# WasteInfoBoard_V_1_2.net
KiCad netlist of a schematic drawn in EAGLE
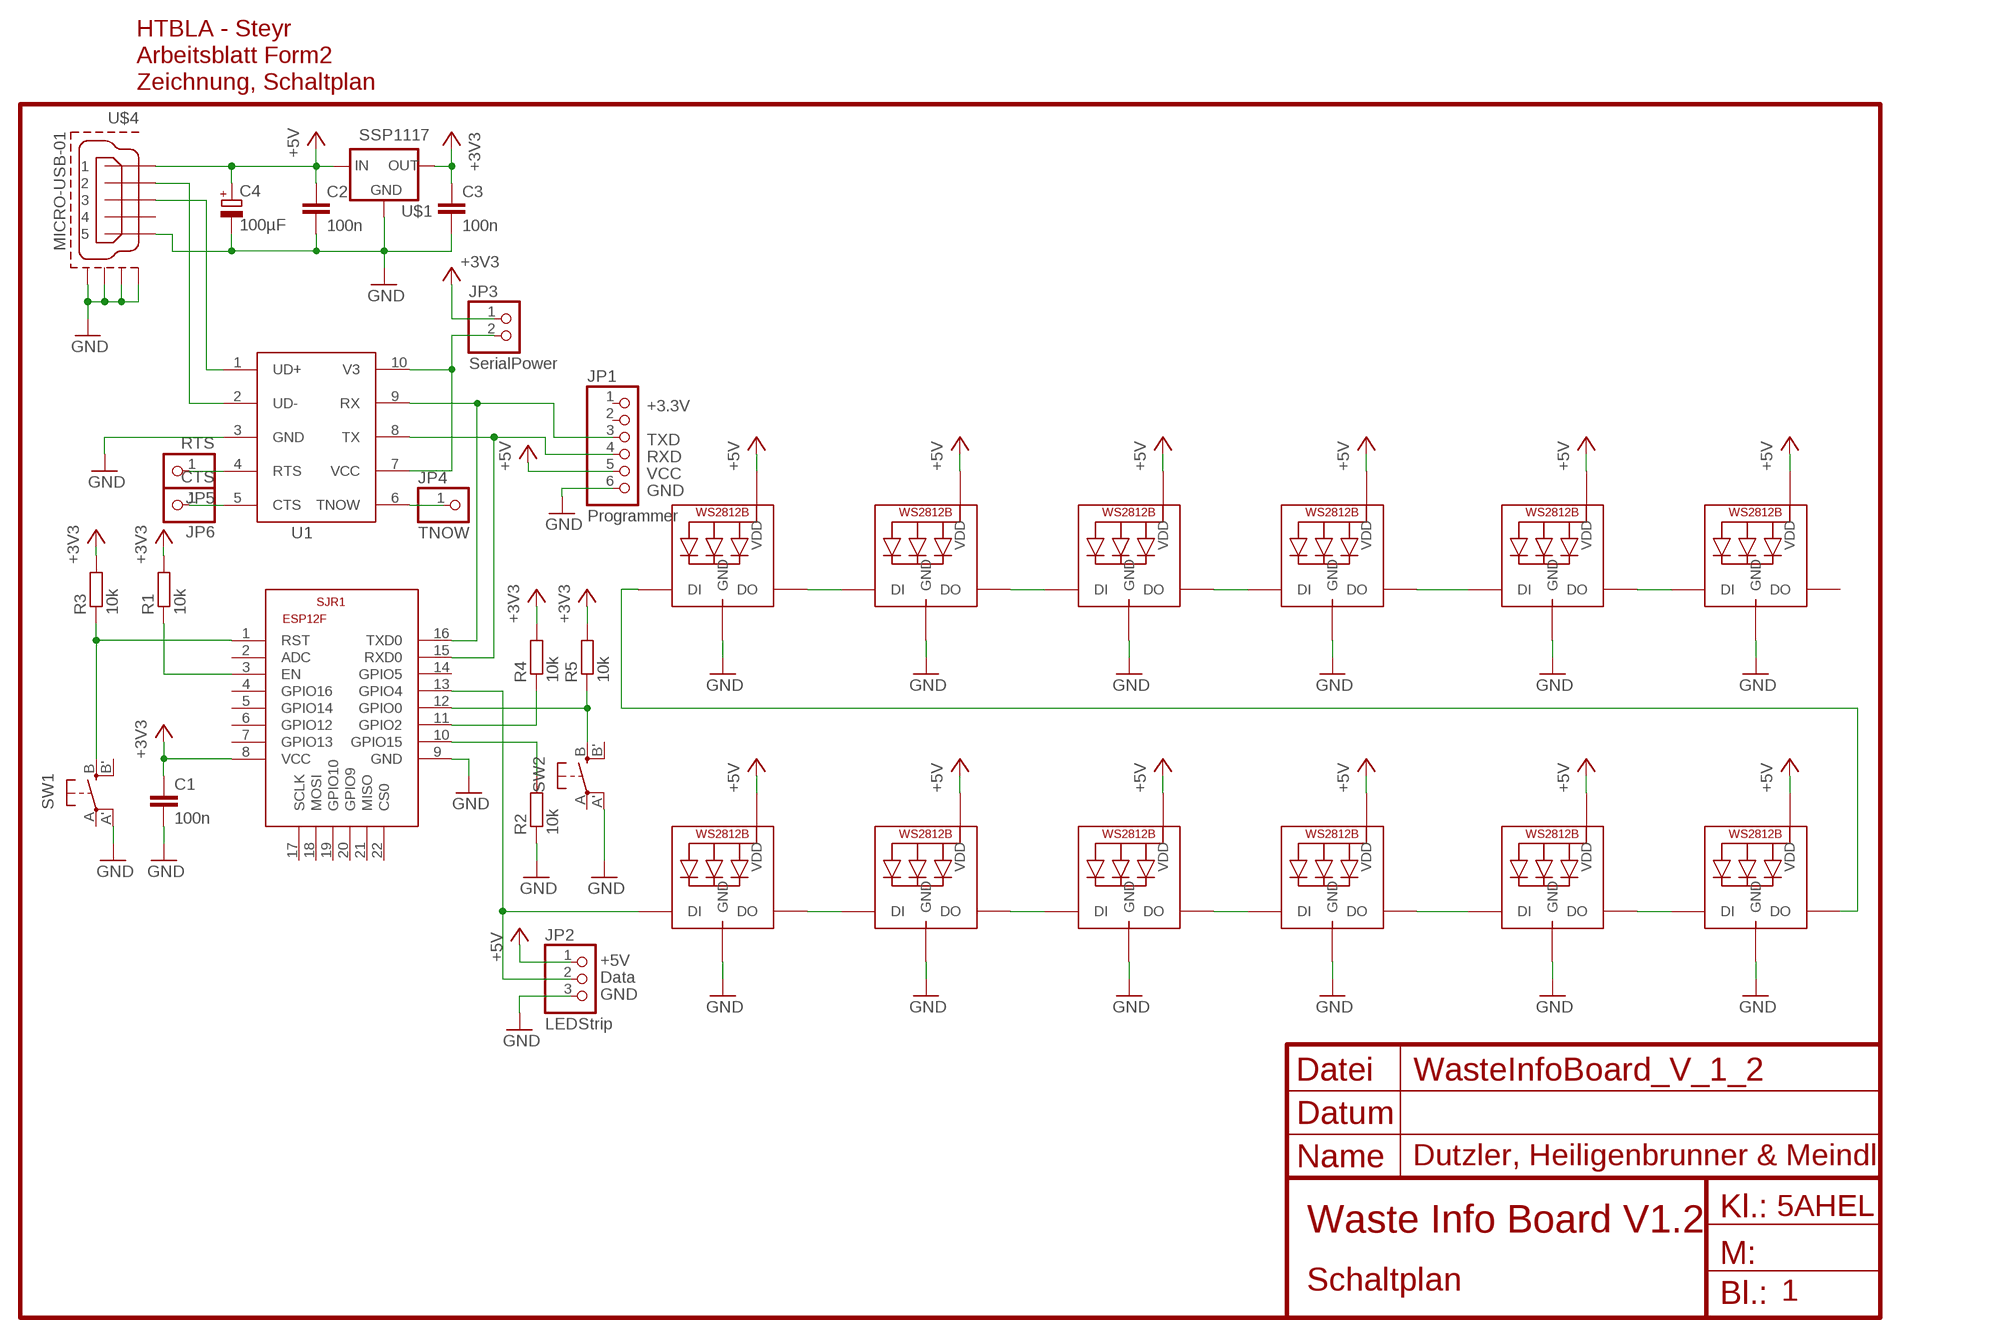
[diagram p0: schematic, sheet 1]

(export (version "E")
  (design (tool "Eeschema 10.0.6"))
  (components
    (comp (ref "C1")
      (value "100n")
      (footprint "eagle-import:C0805")
      (libsource (lib "eagle-import") (part "C-EUC0805"))
    )
    (comp (ref "C2")
      (value "100n")
      (footprint "eagle-import:C0805")
      (libsource (lib "eagle-import") (part "C-EUC0805"))
    )
    (comp (ref "C3")
      (value "100n")
      (footprint "eagle-import:C0805")
      (libsource (lib "eagle-import") (part "C-EUC0805"))
    )
    (comp (ref "C4")
      (value "100µF")
      (footprint "eagle-import:175TMP-0808")
      (libsource (lib "eagle-import") (part "CPOL-EU175TMP-0808"))
    )
    (comp (ref "JP1")
      (value "Programmer")
      (footprint "eagle-import:1X06")
      (libsource (lib "eagle-import") (part "PINHD-1X6"))
    )
    (comp (ref "JP2")
      (value "LEDStrip")
      (footprint "eagle-import:1X03")
      (libsource (lib "eagle-import") (part "PINHD-1X3"))
    )
    (comp (ref "JP3")
      (value "SerialPower")
      (footprint "eagle-import:1X02")
      (libsource (lib "eagle-import") (part "PINHD-1X2"))
    )
    (comp (ref "JP4")
      (value "TNOW")
      (footprint "eagle-import:1X01")
      (libsource (lib "eagle-import") (part "PINHD-1X1"))
    )
    (comp (ref "JP5")
      (value "RTS")
      (footprint "eagle-import:1X01")
      (libsource (lib "eagle-import") (part "PINHD-1X1"))
    )
    (comp (ref "JP6")
      (value "CTS")
      (footprint "eagle-import:1X01")
      (libsource (lib "eagle-import") (part "PINHD-1X1"))
    )
    (comp (ref "LED1")
      (value "WS2812B5050")
      (footprint "eagle-import:WS2812B")
      (libsource (lib "eagle-import") (part "WS2812B5050"))
    )
    (comp (ref "LED2")
      (value "WS2812B5050")
      (footprint "eagle-import:WS2812B")
      (libsource (lib "eagle-import") (part "WS2812B5050"))
    )
    (comp (ref "LED3")
      (value "WS2812B5050")
      (footprint "eagle-import:WS2812B")
      (libsource (lib "eagle-import") (part "WS2812B5050"))
    )
    (comp (ref "LED4")
      (value "WS2812B5050")
      (footprint "eagle-import:WS2812B")
      (libsource (lib "eagle-import") (part "WS2812B5050"))
    )
    (comp (ref "LED5")
      (value "WS2812B5050")
      (footprint "eagle-import:WS2812B")
      (libsource (lib "eagle-import") (part "WS2812B5050"))
    )
    (comp (ref "LED6")
      (value "WS2812B5050")
      (footprint "eagle-import:WS2812B")
      (libsource (lib "eagle-import") (part "WS2812B5050"))
    )
    (comp (ref "LED7")
      (value "WS2812B5050")
      (footprint "eagle-import:WS2812B")
      (libsource (lib "eagle-import") (part "WS2812B5050"))
    )
    (comp (ref "LED8")
      (value "WS2812B5050")
      (footprint "eagle-import:WS2812B")
      (libsource (lib "eagle-import") (part "WS2812B5050"))
    )
    (comp (ref "LED9")
      (value "WS2812B5050")
      (footprint "eagle-import:WS2812B")
      (libsource (lib "eagle-import") (part "WS2812B5050"))
    )
    (comp (ref "LED10")
      (value "WS2812B5050")
      (footprint "eagle-import:WS2812B")
      (libsource (lib "eagle-import") (part "WS2812B5050"))
    )
    (comp (ref "LED11")
      (value "WS2812B5050")
      (footprint "eagle-import:WS2812B")
      (libsource (lib "eagle-import") (part "WS2812B5050"))
    )
    (comp (ref "LED12")
      (value "WS2812B5050")
      (footprint "eagle-import:WS2812B")
      (libsource (lib "eagle-import") (part "WS2812B5050"))
    )
    (comp (ref "R1")
      (value "10k")
      (footprint "eagle-import:R0805")
      (libsource (lib "eagle-import") (part "R-EUR0805"))
    )
    (comp (ref "R2")
      (value "10k")
      (footprint "eagle-import:R0805")
      (libsource (lib "eagle-import") (part "R-EUR0805"))
    )
    (comp (ref "R3")
      (value "10k")
      (footprint "eagle-import:R0805")
      (libsource (lib "eagle-import") (part "R-EUR0805"))
    )
    (comp (ref "R4")
      (value "10k")
      (footprint "eagle-import:R0805")
      (libsource (lib "eagle-import") (part "R-EUR0805"))
    )
    (comp (ref "R5")
      (value "10k")
      (footprint "eagle-import:R0805")
      (libsource (lib "eagle-import") (part "R-EUR0805"))
    )
    (comp (ref "SJR1")
      (value "ESP8266")
      (footprint "eagle-import:ESP8266-ESP12E")
      (libsource (lib "eagle-import") (part "ESP8266-12EESP12E"))
    )
    (comp (ref "SW1")
      (value "SPST_TACT-EVQQ2")
      (footprint "eagle-import:EVQ-Q2")
      (libsource (lib "eagle-import") (part "SPST_TACT-EVQQ2"))
    )
    (comp (ref "SW2")
      (value "SPST_TACT-EVQQ2")
      (footprint "eagle-import:EVQ-Q2")
      (libsource (lib "eagle-import") (part "SPST_TACT-EVQQ2"))
    )
    (comp (ref "U$1")
      (value "SSP1117")
      (footprint "eagle-import:SOT223")
      (libsource (lib "eagle-import") (part "SSP1117-3.3V"))
    )
    (comp (ref "U$4")
      (value "MICRO-USB-01")
      (footprint "eagle-import:47589-0001")
      (libsource (lib "eagle-import") (part "MICRO-USB-RECEPTACLE47589-0001"))
    )
    (comp (ref "U1")
      (value "CH340ESMD")
      (footprint "eagle-import:MSOP10")
      (libsource (lib "eagle-import") (part "CH340ESMD"))
    )
  )
  (nets
    (net (code "1") (name "+3V3") (class "Default")
      (node (ref "C1") (pin "1") (pinfunction "1_1") (pintype "passive"))
      (node (ref "C3") (pin "1") (pinfunction "1_1") (pintype "passive"))
      (node (ref "JP3") (pin "1") (pinfunction "1_1") (pintype "passive"))
      (node (ref "R1") (pin "2") (pinfunction "2_2") (pintype "passive"))
      (node (ref "R3") (pin "2") (pinfunction "2_2") (pintype "passive"))
      (node (ref "R4") (pin "2") (pinfunction "2_2") (pintype "passive"))
      (node (ref "R5") (pin "2") (pinfunction "2_2") (pintype "passive"))
      (node (ref "SJR1") (pin "8") (pinfunction "VCC_8") (pintype "bidirectional"))
      (node (ref "U$1") (pin "2") (pinfunction "OUT_2") (pintype "passive"))
    )
    (net (code "2") (name "+5V") (class "Default")
      (node (ref "C2") (pin "1") (pinfunction "1_1") (pintype "passive"))
      (node (ref "C4") (pin "+") (pinfunction "+_+") (pintype "passive"))
      (node (ref "JP1") (pin "5") (pinfunction "5_5") (pintype "passive"))
      (node (ref "JP2") (pin "1") (pinfunction "1_1") (pintype "passive"))
      (node (ref "LED1") (pin "1-VDD") (pinfunction "VDD_1-VDD") (pintype "power_in"))
      (node (ref "LED10") (pin "1-VDD") (pinfunction "VDD_1-VDD") (pintype "power_in"))
      (node (ref "LED11") (pin "1-VDD") (pinfunction "VDD_1-VDD") (pintype "power_in"))
      (node (ref "LED12") (pin "1-VDD") (pinfunction "VDD_1-VDD") (pintype "power_in"))
      (node (ref "LED2") (pin "1-VDD") (pinfunction "VDD_1-VDD") (pintype "power_in"))
      (node (ref "LED3") (pin "1-VDD") (pinfunction "VDD_1-VDD") (pintype "power_in"))
      (node (ref "LED4") (pin "1-VDD") (pinfunction "VDD_1-VDD") (pintype "power_in"))
      (node (ref "LED5") (pin "1-VDD") (pinfunction "VDD_1-VDD") (pintype "power_in"))
      (node (ref "LED6") (pin "1-VDD") (pinfunction "VDD_1-VDD") (pintype "power_in"))
      (node (ref "LED7") (pin "1-VDD") (pinfunction "VDD_1-VDD") (pintype "power_in"))
      (node (ref "LED8") (pin "1-VDD") (pinfunction "VDD_1-VDD") (pintype "power_in"))
      (node (ref "LED9") (pin "1-VDD") (pinfunction "VDD_1-VDD") (pintype "power_in"))
      (node (ref "U$1") (pin "3") (pinfunction "IN_3") (pintype "input"))
      (node (ref "U$4") (pin "1") (pinfunction "1_1") (pintype "input"))
    )
    (net (code "3") (name "GND") (class "Default")
      (node (ref "C1") (pin "2") (pinfunction "2_2") (pintype "passive"))
      (node (ref "C2") (pin "2") (pinfunction "2_2") (pintype "passive"))
      (node (ref "C3") (pin "2") (pinfunction "2_2") (pintype "passive"))
      (node (ref "C4") (pin "-") (pinfunction "-_-") (pintype "passive"))
      (node (ref "JP1") (pin "6") (pinfunction "6_6") (pintype "passive"))
      (node (ref "JP2") (pin "3") (pinfunction "3_3") (pintype "passive"))
      (node (ref "LED1") (pin "3-GND") (pinfunction "GND_3-GND") (pintype "power_in"))
      (node (ref "LED10") (pin "3-GND") (pinfunction "GND_3-GND") (pintype "power_in"))
      (node (ref "LED11") (pin "3-GND") (pinfunction "GND_3-GND") (pintype "power_in"))
      (node (ref "LED12") (pin "3-GND") (pinfunction "GND_3-GND") (pintype "power_in"))
      (node (ref "LED2") (pin "3-GND") (pinfunction "GND_3-GND") (pintype "power_in"))
      (node (ref "LED3") (pin "3-GND") (pinfunction "GND_3-GND") (pintype "power_in"))
      (node (ref "LED4") (pin "3-GND") (pinfunction "GND_3-GND") (pintype "power_in"))
      (node (ref "LED5") (pin "3-GND") (pinfunction "GND_3-GND") (pintype "power_in"))
      (node (ref "LED6") (pin "3-GND") (pinfunction "GND_3-GND") (pintype "power_in"))
      (node (ref "LED7") (pin "3-GND") (pinfunction "GND_3-GND") (pintype "power_in"))
      (node (ref "LED8") (pin "3-GND") (pinfunction "GND_3-GND") (pintype "power_in"))
      (node (ref "LED9") (pin "3-GND") (pinfunction "GND_3-GND") (pintype "power_in"))
      (node (ref "R2") (pin "1") (pinfunction "1_1") (pintype "passive"))
      (node (ref "SJR1") (pin "9") (pinfunction "GND_9") (pintype "bidirectional"))
      (node (ref "SW1") (pin "A'") (pinfunction "P1_A'") (pintype "passive"))
      (node (ref "SW2") (pin "A'") (pinfunction "P1_A'") (pintype "passive"))
      (node (ref "U$1") (pin "1") (pinfunction "GND_1") (pintype "input"))
      (node (ref "U$4") (pin "5") (pinfunction "5_5") (pintype "input"))
      (node (ref "U$4") (pin "CASING1") (pinfunction "GND1_CASING1") (pintype "bidirectional"))
      (node (ref "U$4") (pin "CASING2") (pinfunction "GND2_CASING2") (pintype "bidirectional"))
      (node (ref "U$4") (pin "CASING3") (pinfunction "GND3_CASING3") (pintype "bidirectional"))
      (node (ref "U$4") (pin "CASING4") (pinfunction "GND4_CASING4") (pintype "bidirectional"))
      (node (ref "U1") (pin "3") (pinfunction "GND_3") (pintype "power_in"))
    )
    (net (code "4") (name "Net-(LED1-DI)") (class "Default")
      (node (ref "JP2") (pin "2") (pinfunction "2_2") (pintype "passive"))
      (node (ref "LED1") (pin "4-DIN") (pinfunction "DI_4-DIN") (pintype "input"))
      (node (ref "SJR1") (pin "13") (pinfunction "GPIO4_13") (pintype "bidirectional"))
    )
    (net (code "5") (name "Net-(LED1-DO)") (class "Default")
      (node (ref "LED1") (pin "2-DOUT") (pinfunction "DO_2-DOUT") (pintype "output"))
      (node (ref "LED2") (pin "4-DIN") (pinfunction "DI_4-DIN") (pintype "input"))
    )
    (net (code "6") (name "Net-(LED2-DO)") (class "Default")
      (node (ref "LED2") (pin "2-DOUT") (pinfunction "DO_2-DOUT") (pintype "output"))
      (node (ref "LED3") (pin "4-DIN") (pinfunction "DI_4-DIN") (pintype "input"))
    )
    (net (code "7") (name "Net-(LED3-DO)") (class "Default")
      (node (ref "LED3") (pin "2-DOUT") (pinfunction "DO_2-DOUT") (pintype "output"))
      (node (ref "LED4") (pin "4-DIN") (pinfunction "DI_4-DIN") (pintype "input"))
    )
    (net (code "8") (name "Net-(LED4-DO)") (class "Default")
      (node (ref "LED4") (pin "2-DOUT") (pinfunction "DO_2-DOUT") (pintype "output"))
      (node (ref "LED5") (pin "4-DIN") (pinfunction "DI_4-DIN") (pintype "input"))
    )
    (net (code "9") (name "Net-(LED5-DO)") (class "Default")
      (node (ref "LED5") (pin "2-DOUT") (pinfunction "DO_2-DOUT") (pintype "output"))
      (node (ref "LED6") (pin "4-DIN") (pinfunction "DI_4-DIN") (pintype "input"))
    )
    (net (code "10") (name "Net-(LED6-DO)") (class "Default")
      (node (ref "LED6") (pin "2-DOUT") (pinfunction "DO_2-DOUT") (pintype "output"))
      (node (ref "LED7") (pin "4-DIN") (pinfunction "DI_4-DIN") (pintype "input"))
    )
    (net (code "11") (name "Net-(LED7-DO)") (class "Default")
      (node (ref "LED7") (pin "2-DOUT") (pinfunction "DO_2-DOUT") (pintype "output"))
      (node (ref "LED8") (pin "4-DIN") (pinfunction "DI_4-DIN") (pintype "input"))
    )
    (net (code "12") (name "Net-(LED8-DO)") (class "Default")
      (node (ref "LED8") (pin "2-DOUT") (pinfunction "DO_2-DOUT") (pintype "output"))
      (node (ref "LED9") (pin "4-DIN") (pinfunction "DI_4-DIN") (pintype "input"))
    )
    (net (code "13") (name "Net-(LED10-DI)") (class "Default")
      (node (ref "LED10") (pin "4-DIN") (pinfunction "DI_4-DIN") (pintype "input"))
      (node (ref "LED9") (pin "2-DOUT") (pinfunction "DO_2-DOUT") (pintype "output"))
    )
    (net (code "14") (name "Net-(LED10-DO)") (class "Default")
      (node (ref "LED10") (pin "2-DOUT") (pinfunction "DO_2-DOUT") (pintype "output"))
      (node (ref "LED11") (pin "4-DIN") (pinfunction "DI_4-DIN") (pintype "input"))
    )
    (net (code "15") (name "Net-(LED11-DO)") (class "Default")
      (node (ref "LED11") (pin "2-DOUT") (pinfunction "DO_2-DOUT") (pintype "output"))
      (node (ref "LED12") (pin "4-DIN") (pinfunction "DI_4-DIN") (pintype "input"))
    )
    (net (code "16") (name "Net-(SJR1-EN)") (class "Default")
      (node (ref "R1") (pin "1") (pinfunction "1_1") (pintype "passive"))
      (node (ref "SJR1") (pin "3") (pinfunction "EN_3") (pintype "bidirectional"))
    )
    (net (code "17") (name "Net-(SJR1-GPIO0)") (class "Default")
      (node (ref "R5") (pin "1") (pinfunction "1_1") (pintype "passive"))
      (node (ref "SJR1") (pin "12") (pinfunction "GPIO0_12") (pintype "bidirectional"))
      (node (ref "SW2") (pin "B") (pinfunction "S_B") (pintype "passive"))
    )
    (net (code "18") (name "Net-(SJR1-GPIO2)") (class "Default")
      (node (ref "R4") (pin "1") (pinfunction "1_1") (pintype "passive"))
      (node (ref "SJR1") (pin "11") (pinfunction "GPIO2_11") (pintype "bidirectional"))
    )
    (net (code "19") (name "Net-(SJR1-GPIO15)") (class "Default")
      (node (ref "R2") (pin "2") (pinfunction "2_2") (pintype "passive"))
      (node (ref "SJR1") (pin "10") (pinfunction "GPIO15_10") (pintype "bidirectional"))
    )
    (net (code "20") (name "Net-(SJR1-RST)") (class "Default")
      (node (ref "R3") (pin "1") (pinfunction "1_1") (pintype "passive"))
      (node (ref "SJR1") (pin "1") (pinfunction "RST_1") (pintype "bidirectional"))
      (node (ref "SW1") (pin "B") (pinfunction "S_B") (pintype "passive"))
    )
    (net (code "21") (name "Net-(SJR1-RXD0)") (class "Default")
      (node (ref "JP1") (pin "4") (pinfunction "4_4") (pintype "passive"))
      (node (ref "SJR1") (pin "15") (pinfunction "RXD0_15") (pintype "bidirectional"))
      (node (ref "U1") (pin "8") (pinfunction "TX_8") (pintype "output"))
    )
    (net (code "22") (name "Net-(SJR1-TXD0)") (class "Default")
      (node (ref "JP1") (pin "3") (pinfunction "3_3") (pintype "passive"))
      (node (ref "SJR1") (pin "16") (pinfunction "TXD0_16") (pintype "bidirectional"))
      (node (ref "U1") (pin "9") (pinfunction "RX_9") (pintype "input"))
    )
    (net (code "23") (name "Net-(U1-CTS)") (class "Default")
      (node (ref "JP6") (pin "1") (pinfunction "1_1") (pintype "passive"))
      (node (ref "U1") (pin "5") (pinfunction "CTS_5") (pintype "input"))
    )
    (net (code "24") (name "Net-(U1-RTS)") (class "Default")
      (node (ref "JP5") (pin "1") (pinfunction "1_1") (pintype "passive"))
      (node (ref "U1") (pin "4") (pinfunction "RTS_4") (pintype "output"))
    )
    (net (code "25") (name "Net-(U1-TNOW)") (class "Default")
      (node (ref "JP4") (pin "1") (pinfunction "1_1") (pintype "passive"))
      (node (ref "U1") (pin "6") (pinfunction "TNOW_6") (pintype "output"))
    )
    (net (code "26") (name "Net-(U1-UD+)") (class "Default")
      (node (ref "U$4") (pin "3") (pinfunction "3_3") (pintype "input"))
      (node (ref "U1") (pin "1") (pinfunction "UD+_1") (pintype "bidirectional"))
    )
    (net (code "27") (name "Net-(U1-UD-)") (class "Default")
      (node (ref "U$4") (pin "2") (pinfunction "2_2") (pintype "input"))
      (node (ref "U1") (pin "2") (pinfunction "UD-_2") (pintype "bidirectional"))
    )
    (net (code "28") (name "Net-(U1-V3)") (class "Default")
      (node (ref "JP3") (pin "2") (pinfunction "2_2") (pintype "passive"))
      (node (ref "U1") (pin "10") (pinfunction "V3_10") (pintype "power_in"))
      (node (ref "U1") (pin "7") (pinfunction "VCC_7") (pintype "power_in"))
    )
    (net (code "29") (name "unconnected-(JP1-Pad1)") (class "Default")
      (node (ref "JP1") (pin "1") (pinfunction "1_1") (pintype "passive"))
    )
    (net (code "30") (name "unconnected-(JP1-Pad2)") (class "Default")
      (node (ref "JP1") (pin "2") (pinfunction "2_2") (pintype "passive"))
    )
    (net (code "31") (name "unconnected-(LED12-DO-Pad2-DOUT)") (class "Default")
      (node (ref "LED12") (pin "2-DOUT") (pinfunction "DO_2-DOUT") (pintype "output"))
    )
    (net (code "32") (name "unconnected-(SJR1-ADC-Pad2)") (class "Default")
      (node (ref "SJR1") (pin "2") (pinfunction "ADC_2") (pintype "bidirectional"))
    )
    (net (code "33") (name "unconnected-(SJR1-CS0-Pad22)") (class "Default")
      (node (ref "SJR1") (pin "22") (pinfunction "CS0_22") (pintype "bidirectional"))
    )
    (net (code "34") (name "unconnected-(SJR1-GPIO5-Pad14)") (class "Default")
      (node (ref "SJR1") (pin "14") (pinfunction "GPIO5_14") (pintype "bidirectional"))
    )
    (net (code "35") (name "unconnected-(SJR1-GPIO9-Pad20)") (class "Default")
      (node (ref "SJR1") (pin "20") (pinfunction "GPIO9_20") (pintype "bidirectional"))
    )
    (net (code "36") (name "unconnected-(SJR1-GPIO10-Pad19)") (class "Default")
      (node (ref "SJR1") (pin "19") (pinfunction "GPIO10_19") (pintype "bidirectional"))
    )
    (net (code "37") (name "unconnected-(SJR1-GPIO12-Pad6)") (class "Default")
      (node (ref "SJR1") (pin "6") (pinfunction "GPIO12_6") (pintype "bidirectional"))
    )
    (net (code "38") (name "unconnected-(SJR1-GPIO13-Pad7)") (class "Default")
      (node (ref "SJR1") (pin "7") (pinfunction "GPIO13_7") (pintype "bidirectional"))
    )
    (net (code "39") (name "unconnected-(SJR1-GPIO14-Pad5)") (class "Default")
      (node (ref "SJR1") (pin "5") (pinfunction "GPIO14_5") (pintype "bidirectional"))
    )
    (net (code "40") (name "unconnected-(SJR1-GPIO16-Pad4)") (class "Default")
      (node (ref "SJR1") (pin "4") (pinfunction "GPIO16_4") (pintype "bidirectional"))
    )
    (net (code "41") (name "unconnected-(SJR1-MISO-Pad21)") (class "Default")
      (node (ref "SJR1") (pin "21") (pinfunction "MISO_21") (pintype "bidirectional"))
    )
    (net (code "42") (name "unconnected-(SJR1-MOSI-Pad18)") (class "Default")
      (node (ref "SJR1") (pin "18") (pinfunction "MOSI_18") (pintype "bidirectional"))
    )
    (net (code "43") (name "unconnected-(SJR1-SCLK-Pad17)") (class "Default")
      (node (ref "SJR1") (pin "17") (pinfunction "SCLK_17") (pintype "bidirectional"))
    )
    (net (code "44") (name "unconnected-(SW1-P-PadA)") (class "Default")
      (node (ref "SW1") (pin "A") (pinfunction "P_A") (pintype "passive"))
    )
    (net (code "45") (name "unconnected-(SW1-S1-PadB')") (class "Default")
      (node (ref "SW1") (pin "B'") (pinfunction "S1_B'") (pintype "passive"))
    )
    (net (code "46") (name "unconnected-(SW2-P-PadA)") (class "Default")
      (node (ref "SW2") (pin "A") (pinfunction "P_A") (pintype "passive"))
    )
    (net (code "47") (name "unconnected-(SW2-S1-PadB')") (class "Default")
      (node (ref "SW2") (pin "B'") (pinfunction "S1_B'") (pintype "passive"))
    )
    (net (code "48") (name "unconnected-(U$4-Pad4)") (class "Default")
      (node (ref "U$4") (pin "4") (pinfunction "4_4") (pintype "input"))
    )
  )
)
